# StrongPCB_mixed.net
KiCad netlist of a schematic drawn in Altium Designer
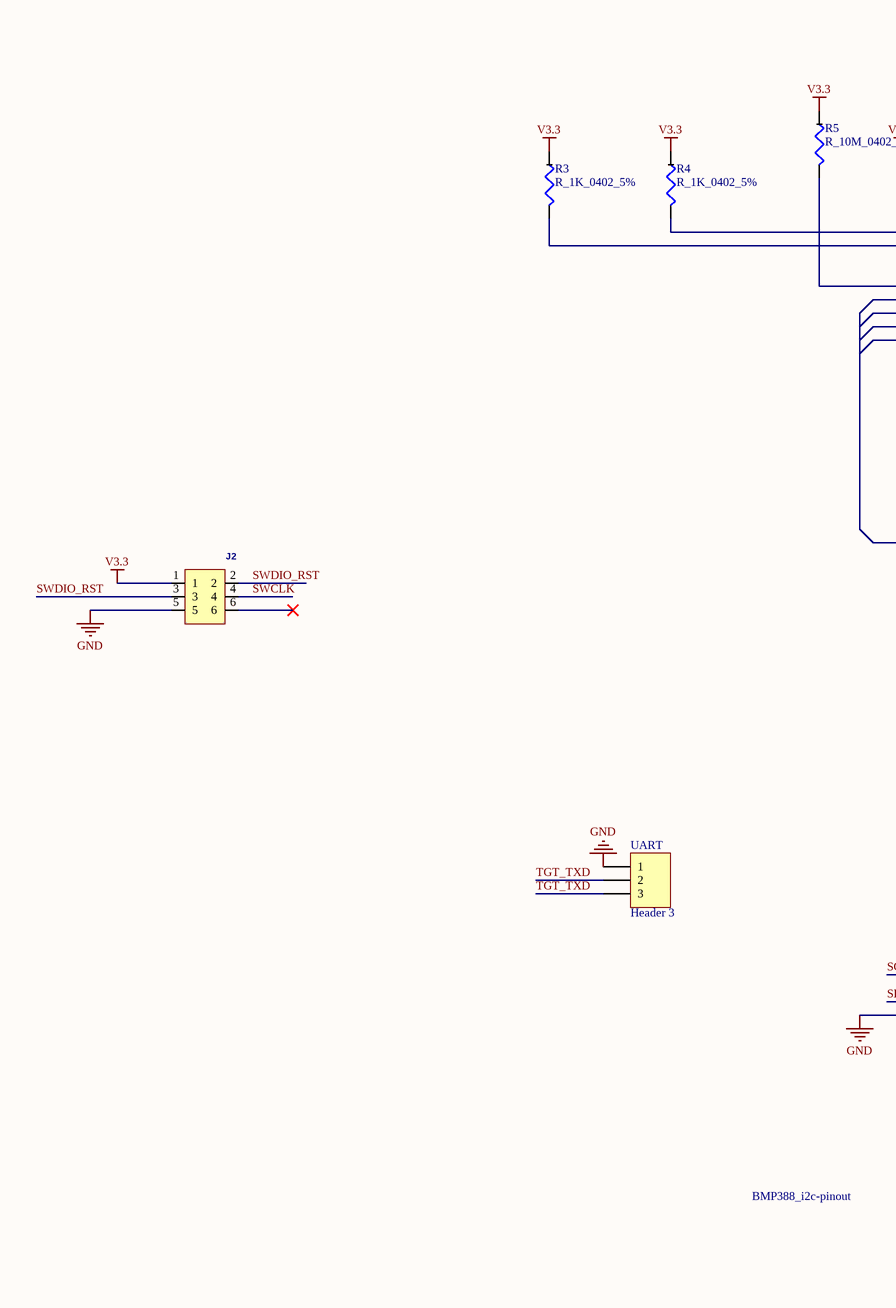
[diagram p0: StrongPCB_mixed.SchDoc, left]
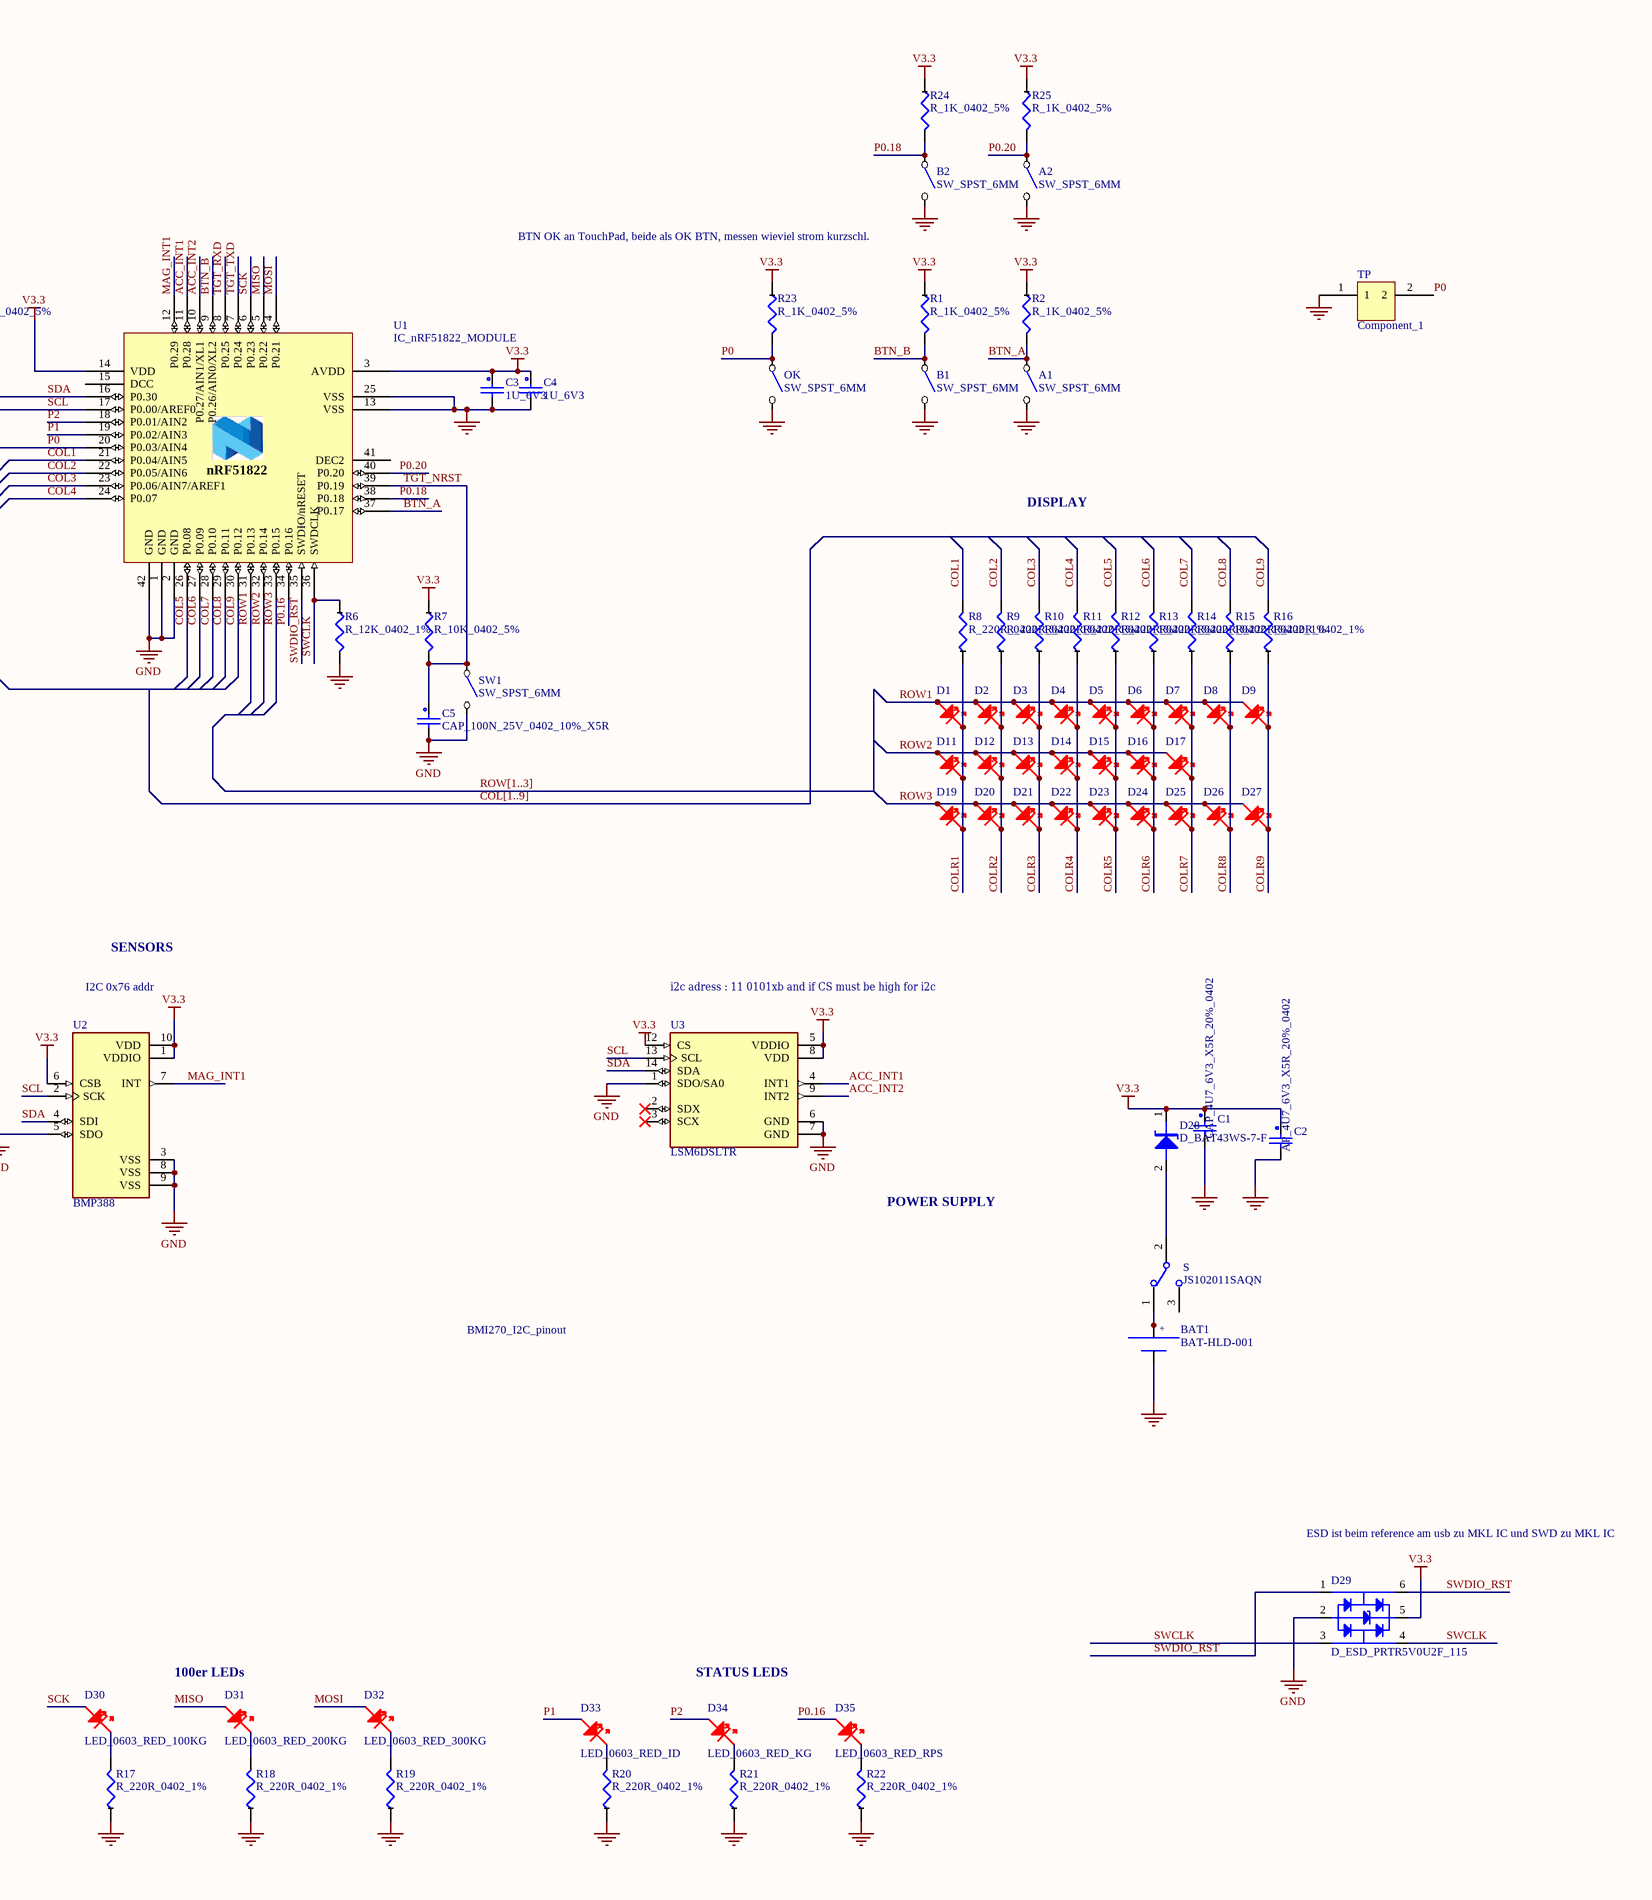
[diagram p1: StrongPCB_mixed.SchDoc, right]

(export (version "E")
  (design (tool "Eeschema 10.0.6"))
  (components
    (comp (ref "A1")
      (value "SW_SPST_6MM")
      (footprint "SW_FSM4JSMA")
      (description "SPST SWITCH 6MM")
      (fields (field (name "PART") "FSM4JSMA") (field (name "MANUFACTURER") "TE CONNECTIVITY / ALCOSWITCH"))
      (libsource (lib "Modulebit_open_V0.4") (part "SW_SPST_6MM"))
    )
    (comp (ref "A2")
      (value "SW_SPST_6MM")
      (footprint "SW_FSM4JSMA")
      (description "SPST SWITCH 6MM")
      (fields (field (name "PART") "FSM4JSMA") (field (name "MANUFACTURER") "TE CONNECTIVITY / ALCOSWITCH"))
      (libsource (lib "Modulebit_open_V0.4") (part "SW_SPST_6MM"))
    )
    (comp (ref "B1")
      (value "SW_SPST_6MM")
      (footprint "SW_FSM4JSMA")
      (description "SPST SWITCH 6MM")
      (fields (field (name "PART") "FSM4JSMA") (field (name "MANUFACTURER") "TE CONNECTIVITY / ALCOSWITCH"))
      (libsource (lib "Modulebit_open_V0.4") (part "SW_SPST_6MM"))
    )
    (comp (ref "B2")
      (value "SW_SPST_6MM")
      (footprint "SW_FSM4JSMA")
      (description "SPST SWITCH 6MM")
      (fields (field (name "PART") "FSM4JSMA") (field (name "MANUFACTURER") "TE CONNECTIVITY / ALCOSWITCH"))
      (libsource (lib "Modulebit_open_V0.4") (part "SW_SPST_6MM"))
    )
    (comp (ref "BAT1")
      (value "BAT-HLD-001")
      (footprint "BAT-HLD-001")
      (description "Battery Retainer Coin, 20.0mm 1 Cell SMD _SMT_ Tab")
      (fields
        (field (name "DIGI-KEY_PART_NUMBER") "BAT-HLD-001-TRCT-ND")
        (field (name "MF") "Linx Technologies")
      )
      (libsource (lib "BAT-HLD-001") (part "BAT-HLD-001"))
    )
    (comp (ref "C1")
      (value "CAP_4U7_6V3_X5R_20%_0402")
      (footprint "c_0402")
      (fields (field (name "PART") "C1005X5R0J475M") (field (name "MANUFACTURER") "TDK"))
      (libsource (lib "Modulebit_open_V0.4") (part "CAP_4U7_6V3_X5R_20%_0402"))
    )
    (comp (ref "C2")
      (value "AP_4U7_6V3_X5R_20%_0402")
      (footprint "c_0402")
      (description "CAP_4U7_6V3_X5R_20%_0402")
      (fields (field (name "PART") "C1005X5R0J475M") (field (name "MANUFACTURER") "TDK"))
      (libsource (lib "Modulebit_open_V0.4") (part "CAP_4U7_6V3_X5R_20%_0402"))
    )
    (comp (ref "C3")
      (value "1U_6V3")
      (footprint "C_0402")
      (description "CAP_1u_6V3_0402_10%_X6S")
      (fields (field (name "MANUFACTURER") "YAGEO") (field (name "PART") "CC0402KRX7R7BB104"))
      (libsource (lib "Modulebit_open_V0.4") (part "CAP_1u_6V3_0402_10%_X6S"))
    )
    (comp (ref "C4")
      (value "1U_6V3")
      (footprint "C_0402")
      (description "CAP_1u_6V3_0402_10%_X6S")
      (fields (field (name "MANUFACTURER") "YAGEO") (field (name "PART") "CC0402KRX7R7BB104"))
      (libsource (lib "Modulebit_open_V0.4") (part "CAP_1u_6V3_0402_10%_X6S"))
    )
    (comp (ref "C5")
      (value "CAP_100N_25V_0402_10%_X5R")
      (footprint "C_0402")
      (fields (field (name "PART") "TMK105BJ104KV-F") (field (name "MANUFACTURER") "TAIYO YUDEN"))
      (libsource (lib "Modulebit_open_V0.4") (part "CAP_100N_25V_0402_10%_X5R"))
    )
    (comp (ref "D1")
      (value "LED_0603_RED")
      (footprint "LED_0603_RED")
      (description "LED RED 0603")
      (fields (field (name "PART") "KP-1608SURC") (field (name "MANUFACTURER") "KINGBRIGHT"))
      (libsource (lib "Modulebit_open_V0.4") (part "LED_0603_RED"))
    )
    (comp (ref "D2")
      (value "LED_0603_RED")
      (footprint "LED_0603_RED")
      (description "LED RED 0603")
      (fields (field (name "PART") "KP-1608SURC") (field (name "MANUFACTURER") "KINGBRIGHT"))
      (libsource (lib "Modulebit_open_V0.4") (part "LED_0603_RED"))
    )
    (comp (ref "D3")
      (value "LED_0603_RED")
      (footprint "LED_0603_RED")
      (description "LED RED 0603")
      (fields (field (name "PART") "KP-1608SURC") (field (name "MANUFACTURER") "KINGBRIGHT"))
      (libsource (lib "Modulebit_open_V0.4") (part "LED_0603_RED"))
    )
    (comp (ref "D4")
      (value "LED_0603_RED")
      (footprint "LED_0603_RED")
      (description "LED RED 0603")
      (fields (field (name "PART") "KP-1608SURC") (field (name "MANUFACTURER") "KINGBRIGHT"))
      (libsource (lib "Modulebit_open_V0.4") (part "LED_0603_RED"))
    )
    (comp (ref "D5")
      (value "LED_0603_RED")
      (footprint "LED_0603_RED")
      (description "LED RED 0603")
      (fields (field (name "PART") "KP-1608SURC") (field (name "MANUFACTURER") "KINGBRIGHT"))
      (libsource (lib "Modulebit_open_V0.4") (part "LED_0603_RED"))
    )
    (comp (ref "D6")
      (value "LED_0603_RED")
      (footprint "LED_0603_RED")
      (description "LED RED 0603")
      (fields (field (name "PART") "KP-1608SURC") (field (name "MANUFACTURER") "KINGBRIGHT"))
      (libsource (lib "Modulebit_open_V0.4") (part "LED_0603_RED"))
    )
    (comp (ref "D7")
      (value "LED_0603_RED")
      (footprint "LED_0603_RED")
      (description "LED RED 0603")
      (fields (field (name "PART") "KP-1608SURC") (field (name "MANUFACTURER") "KINGBRIGHT"))
      (libsource (lib "Modulebit_open_V0.4") (part "LED_0603_RED"))
    )
    (comp (ref "D8")
      (value "LED_0603_RED")
      (footprint "LED_0603_RED")
      (description "LED RED 0603")
      (fields (field (name "PART") "KP-1608SURC") (field (name "MANUFACTURER") "KINGBRIGHT"))
      (libsource (lib "Modulebit_open_V0.4") (part "LED_0603_RED"))
    )
    (comp (ref "D9")
      (value "LED_0603_RED")
      (footprint "LED_0603_RED")
      (description "LED RED 0603")
      (fields (field (name "PART") "KP-1608SURC") (field (name "MANUFACTURER") "KINGBRIGHT"))
      (libsource (lib "Modulebit_open_V0.4") (part "LED_0603_RED"))
    )
    (comp (ref "D11")
      (value "LED_0603_RED")
      (footprint "LED_0603_RED")
      (description "LED RED 0603")
      (fields (field (name "PART") "KP-1608SURC") (field (name "MANUFACTURER") "KINGBRIGHT"))
      (libsource (lib "Modulebit_open_V0.4") (part "LED_0603_RED"))
    )
    (comp (ref "D12")
      (value "LED_0603_RED")
      (footprint "LED_0603_RED")
      (description "LED RED 0603")
      (fields (field (name "PART") "KP-1608SURC") (field (name "MANUFACTURER") "KINGBRIGHT"))
      (libsource (lib "Modulebit_open_V0.4") (part "LED_0603_RED"))
    )
    (comp (ref "D13")
      (value "LED_0603_RED")
      (footprint "LED_0603_RED")
      (description "LED RED 0603")
      (fields (field (name "PART") "KP-1608SURC") (field (name "MANUFACTURER") "KINGBRIGHT"))
      (libsource (lib "Modulebit_open_V0.4") (part "LED_0603_RED"))
    )
    (comp (ref "D14")
      (value "LED_0603_RED")
      (footprint "LED_0603_RED")
      (description "LED RED 0603")
      (fields (field (name "PART") "KP-1608SURC") (field (name "MANUFACTURER") "KINGBRIGHT"))
      (libsource (lib "Modulebit_open_V0.4") (part "LED_0603_RED"))
    )
    (comp (ref "D15")
      (value "LED_0603_RED")
      (footprint "LED_0603_RED")
      (description "LED RED 0603")
      (fields (field (name "PART") "KP-1608SURC") (field (name "MANUFACTURER") "KINGBRIGHT"))
      (libsource (lib "Modulebit_open_V0.4") (part "LED_0603_RED"))
    )
    (comp (ref "D16")
      (value "LED_0603_RED")
      (footprint "LED_0603_RED")
      (description "LED RED 0603")
      (fields (field (name "PART") "KP-1608SURC") (field (name "MANUFACTURER") "KINGBRIGHT"))
      (libsource (lib "Modulebit_open_V0.4") (part "LED_0603_RED"))
    )
    (comp (ref "D17")
      (value "LED_0603_RED")
      (footprint "LED_0603_RED")
      (description "LED RED 0603")
      (fields (field (name "PART") "KP-1608SURC") (field (name "MANUFACTURER") "KINGBRIGHT"))
      (libsource (lib "Modulebit_open_V0.4") (part "LED_0603_RED"))
    )
    (comp (ref "D19")
      (value "LED_0603_RED")
      (footprint "LED_0603_RED")
      (description "LED RED 0603")
      (fields (field (name "PART") "KP-1608SURC") (field (name "MANUFACTURER") "KINGBRIGHT"))
      (libsource (lib "Modulebit_open_V0.4") (part "LED_0603_RED"))
    )
    (comp (ref "D20")
      (value "LED_0603_RED")
      (footprint "LED_0603_RED")
      (description "LED RED 0603")
      (fields (field (name "PART") "KP-1608SURC") (field (name "MANUFACTURER") "KINGBRIGHT"))
      (libsource (lib "Modulebit_open_V0.4") (part "LED_0603_RED"))
    )
    (comp (ref "D21")
      (value "LED_0603_RED")
      (footprint "LED_0603_RED")
      (description "LED RED 0603")
      (fields (field (name "PART") "KP-1608SURC") (field (name "MANUFACTURER") "KINGBRIGHT"))
      (libsource (lib "Modulebit_open_V0.4") (part "LED_0603_RED"))
    )
    (comp (ref "D22")
      (value "LED_0603_RED")
      (footprint "LED_0603_RED")
      (description "LED RED 0603")
      (fields (field (name "PART") "KP-1608SURC") (field (name "MANUFACTURER") "KINGBRIGHT"))
      (libsource (lib "Modulebit_open_V0.4") (part "LED_0603_RED"))
    )
    (comp (ref "D23")
      (value "LED_0603_RED")
      (footprint "LED_0603_RED")
      (description "LED RED 0603")
      (fields (field (name "PART") "KP-1608SURC") (field (name "MANUFACTURER") "KINGBRIGHT"))
      (libsource (lib "Modulebit_open_V0.4") (part "LED_0603_RED"))
    )
    (comp (ref "D24")
      (value "LED_0603_RED")
      (footprint "LED_0603_RED")
      (description "LED RED 0603")
      (fields (field (name "PART") "KP-1608SURC") (field (name "MANUFACTURER") "KINGBRIGHT"))
      (libsource (lib "Modulebit_open_V0.4") (part "LED_0603_RED"))
    )
    (comp (ref "D25")
      (value "LED_0603_RED")
      (footprint "LED_0603_RED")
      (description "LED RED 0603")
      (fields (field (name "PART") "KP-1608SURC") (field (name "MANUFACTURER") "KINGBRIGHT"))
      (libsource (lib "Modulebit_open_V0.4") (part "LED_0603_RED"))
    )
    (comp (ref "D26")
      (value "LED_0603_RED")
      (footprint "LED_0603_RED")
      (description "LED RED 0603")
      (fields (field (name "PART") "KP-1608SURC") (field (name "MANUFACTURER") "KINGBRIGHT"))
      (libsource (lib "Modulebit_open_V0.4") (part "LED_0603_RED"))
    )
    (comp (ref "D27")
      (value "LED_0603_RED")
      (footprint "LED_0603_RED")
      (description "LED RED 0603")
      (fields (field (name "PART") "KP-1608SURC") (field (name "MANUFACTURER") "KINGBRIGHT"))
      (libsource (lib "Modulebit_open_V0.4") (part "LED_0603_RED"))
    )
    (comp (ref "D28")
      (value "D_BAT43WS-7-F")
      (footprint "SOD323")
      (description "Schottky 200mA 30V 0.5uA@25Vr")
      (fields (field (name "MANUFACTURER") "Diodes Incorporated") (field (name "PART") "BAT43WS-7-F"))
      (libsource (lib "Modulebit_open_V0.4") (part "D_BAT43WS-7-F"))
    )
    (comp (ref "D29")
      (value "D_ESD_PRTR5V0U2F_115")
      (footprint "SOT886")
      (description "Ultra low capacitance double rail-to-rail ESD protection")
      (fields (field (name "MANUFACTURER") "NXP") (field (name "PART") "PRTR5V0U2F_115"))
      (libsource (lib "Modulebit_open_V0.4") (part "D_ESD_PRTR5V0U2F_115"))
    )
    (comp (ref "D30")
      (value "LED_0603_RED_100KG")
      (footprint "LED_0603_RED")
      (description "LED RED 0603")
      (fields (field (name "PART") "KP-1608SURC") (field (name "MANUFACTURER") "KINGBRIGHT"))
      (libsource (lib "Modulebit_open_V0.4") (part "LED_0603_RED"))
    )
    (comp (ref "D31")
      (value "LED_0603_RED_200KG")
      (footprint "LED_0603_RED")
      (description "LED RED 0603")
      (fields (field (name "PART") "KP-1608SURC") (field (name "MANUFACTURER") "KINGBRIGHT"))
      (libsource (lib "Modulebit_open_V0.4") (part "LED_0603_RED"))
    )
    (comp (ref "D32")
      (value "LED_0603_RED_300KG")
      (footprint "LED_0603_RED")
      (description "LED RED 0603")
      (fields (field (name "PART") "KP-1608SURC") (field (name "MANUFACTURER") "KINGBRIGHT"))
      (libsource (lib "Modulebit_open_V0.4") (part "LED_0603_RED"))
    )
    (comp (ref "D33")
      (value "LED_0603_RED_ID")
      (footprint "LED_0603_RED")
      (description "LED RED 0603")
      (fields (field (name "PART") "KP-1608SURC") (field (name "MANUFACTURER") "KINGBRIGHT"))
      (libsource (lib "Modulebit_open_V0.4") (part "LED_0603_RED"))
    )
    (comp (ref "D34")
      (value "LED_0603_RED_KG")
      (footprint "LED_0603_RED")
      (description "LED RED 0603")
      (fields (field (name "PART") "KP-1608SURC") (field (name "MANUFACTURER") "KINGBRIGHT"))
      (libsource (lib "Modulebit_open_V0.4") (part "LED_0603_RED"))
    )
    (comp (ref "D35")
      (value "LED_0603_RED_RPS")
      (footprint "LED_0603_RED")
      (description "LED RED 0603")
      (fields (field (name "PART") "KP-1608SURC") (field (name "MANUFACTURER") "KINGBRIGHT"))
      (libsource (lib "Modulebit_open_V0.4") (part "LED_0603_RED"))
    )
    (comp (ref "J2")
      (value "Sockets & Adapters J-Link 6-pin Needle Adapter   Source:  Datasheet")
      (footprint "J-Link 6-pin Needle Adapter no legs")
      (fields
        (field (name "MANUFACTURER_PART_NUMBER") "8.06.16")
        (field (name "MOUSER_PART_NUMBER") "943-8.06.16")
      )
      (libsource (lib "J-Link 6-pin") (part "J-Link Connector"))
    )
    (comp (ref "OK")
      (value "SW_SPST_6MM")
      (footprint "SW_FSM4JSMA")
      (description "SPST SWITCH 6MM")
      (fields (field (name "PART") "FSM4JSMA") (field (name "MANUFACTURER") "TE CONNECTIVITY / ALCOSWITCH"))
      (libsource (lib "Modulebit_open_V0.4") (part "SW_SPST_6MM"))
    )
    (comp (ref "R1")
      (value "R_1K_0402_5%")
      (footprint "R_0402")
      (libsource (lib "Modulebit_open_V0.4") (part "R_1K_0402_5%"))
    )
    (comp (ref "R2")
      (value "R_1K_0402_5%")
      (footprint "R_0402")
      (libsource (lib "Modulebit_open_V0.4") (part "R_1K_0402_5%"))
    )
    (comp (ref "R3")
      (value "R_1K_0402_5%")
      (footprint "R_0402")
      (libsource (lib "Modulebit_open_V0.4") (part "R_1K_0402_5%"))
    )
    (comp (ref "R4")
      (value "R_1K_0402_5%")
      (footprint "R_0402")
      (libsource (lib "Modulebit_open_V0.4") (part "R_1K_0402_5%"))
    )
    (comp (ref "R5")
      (value "R_10M_0402_5%")
      (footprint "R_0402")
      (fields (field (name "PART") "RC0603FR-0710ML") (field (name "MANUFACTURER") "YAGEO"))
      (libsource (lib "Modulebit_open_V0.4") (part "R_10M_0402_5%"))
    )
    (comp (ref "R6")
      (value "R_12K_0402_1%")
      (footprint "R_0402")
      (libsource (lib "Modulebit_open_V0.4") (part "R_12K_0402_1%"))
    )
    (comp (ref "R7")
      (value "R_10K_0402_5%")
      (footprint "R_0402")
      (libsource (lib "Modulebit_open_V0.4") (part "R_10K_0402_5%"))
    )
    (comp (ref "R8")
      (value "R_220R_0402_1%")
      (footprint "R_0402")
      (libsource (lib "custom_modulebit_Lib") (part "R_220R_0402_1%"))
    )
    (comp (ref "R9")
      (value "R_220R_0402_1%")
      (footprint "R_0402")
      (libsource (lib "custom_modulebit_Lib") (part "R_220R_0402_1%"))
    )
    (comp (ref "R10")
      (value "R_220R_0402_1%")
      (footprint "R_0402")
      (libsource (lib "custom_modulebit_Lib") (part "R_220R_0402_1%"))
    )
    (comp (ref "R11")
      (value "R_220R_0402_1%")
      (footprint "R_0402")
      (libsource (lib "custom_modulebit_Lib") (part "R_220R_0402_1%"))
    )
    (comp (ref "R12")
      (value "R_220R_0402_1%")
      (footprint "R_0402")
      (libsource (lib "custom_modulebit_Lib") (part "R_220R_0402_1%"))
    )
    (comp (ref "R13")
      (value "R_220R_0402_1%")
      (footprint "R_0402")
      (libsource (lib "custom_modulebit_Lib") (part "R_220R_0402_1%"))
    )
    (comp (ref "R14")
      (value "R_220R_0402_1%")
      (footprint "R_0402")
      (libsource (lib "custom_modulebit_Lib") (part "R_220R_0402_1%"))
    )
    (comp (ref "R15")
      (value "R_220R_0402_1%")
      (footprint "R_0402")
      (libsource (lib "custom_modulebit_Lib") (part "R_220R_0402_1%"))
    )
    (comp (ref "R16")
      (value "R_220R_0402_1%")
      (footprint "R_0402")
      (libsource (lib "custom_modulebit_Lib") (part "R_220R_0402_1%"))
    )
    (comp (ref "R17")
      (value "R_220R_0402_1%")
      (footprint "R_0402")
      (libsource (lib "custom_modulebit_Lib") (part "R_220R_0402_1%"))
    )
    (comp (ref "R18")
      (value "R_220R_0402_1%")
      (footprint "R_0402")
      (libsource (lib "custom_modulebit_Lib") (part "R_220R_0402_1%"))
    )
    (comp (ref "R19")
      (value "R_220R_0402_1%")
      (footprint "R_0402")
      (libsource (lib "custom_modulebit_Lib") (part "R_220R_0402_1%"))
    )
    (comp (ref "R20")
      (value "R_220R_0402_1%")
      (footprint "R_0402")
      (libsource (lib "custom_modulebit_Lib") (part "R_220R_0402_1%"))
    )
    (comp (ref "R21")
      (value "R_220R_0402_1%")
      (footprint "R_0402")
      (libsource (lib "custom_modulebit_Lib") (part "R_220R_0402_1%"))
    )
    (comp (ref "R22")
      (value "R_220R_0402_1%")
      (footprint "R_0402")
      (libsource (lib "custom_modulebit_Lib") (part "R_220R_0402_1%"))
    )
    (comp (ref "R23")
      (value "R_1K_0402_5%")
      (footprint "R_0402")
      (libsource (lib "Modulebit_open_V0.4") (part "R_1K_0402_5%"))
    )
    (comp (ref "R24")
      (value "R_1K_0402_5%")
      (footprint "R_0402")
      (libsource (lib "Modulebit_open_V0.4") (part "R_1K_0402_5%"))
    )
    (comp (ref "R25")
      (value "R_1K_0402_5%")
      (footprint "R_0402")
      (libsource (lib "Modulebit_open_V0.4") (part "R_1K_0402_5%"))
    )
    (comp (ref "S")
      (value "JS102011SAQN")
      (footprint "SW_JS102011SAQN")
      (description "Slide Switch SPDT Surface Mount, Right Angle")
      (fields (field (name "MF") "C&K"))
      (libsource (lib "JS102011SAQN_SWITCH") (part "JS102011SAQN"))
    )
    (comp (ref "SW1")
      (value "SW_SPST_6MM")
      (footprint "SW_FSM4JSMA")
      (description "SPST SWITCH 6MM")
      (fields (field (name "PART") "FSM4JSMA") (field (name "MANUFACTURER") "TE CONNECTIVITY / ALCOSWITCH"))
      (libsource (lib "Modulebit_open_V0.4") (part "SW_SPST_6MM"))
    )
    (comp (ref "TP")
      (value "Component_1")
      (footprint "PCBComponent_1")
      (libsource (lib "TP") (part "Component_1"))
    )
    (comp (ref "U1")
      (value "IC_nRF51822_MODULE")
      (footprint "IC_nRF51822_MODULE_PASTE")
      (description "RF System on a Chip - SoC 2.4GHz BT low Energy 256KB Flash 16KB Ram")
      (fields (field (name "MANUFACTURER") "RAYTAC") (field (name "PART") "MDBT40-256V3"))
      (libsource (lib "Modulebit_open_V0.4") (part "IC_nRF51822_MODULE"))
    )
    (comp (ref "U2")
      (value "BMP388")
      (footprint "PQFN50P200X200X80-10N")
      (description "Pressure Sensor 4.35PSI ~ 18.13PSI _30kPa ~ 125kPa_ Absolute 10-WFLGA")
      (fields (field (name "DIGI-KEY_PART_NUMBER") "828-1079-1-ND") (field (name "MF") "Bosch Sensortec"))
      (libsource (lib "BMP388") (part "BMP388"))
    )
    (comp (ref "U3")
      (value "LSM6DSLTR")
      (footprint "PQFN50P300X250X86-14N")
      (description "Accelerometer, Gyroscope, Temperature, 6 Axis Sensor IÂ²C, SPI Output")
      (fields (field (name "MF") "STMicroelectronics"))
      (libsource (lib "LSM6DSLTR") (part "LSM6DSLTR"))
    )
    (comp (ref "UART")
      (value "Header 3")
      (footprint "HDR1X3")
      (description "Header, 3-Pin")
      (fields (field (name "PUBLISHER") "Altium Limited"))
      (libsource (lib "Miscellaneous Connectors") (part "Header 3"))
    )
  )
  (nets
    (net (code "1") (name "/ACC_INT1") (class "Default")
      (node (ref "U1") (pin "11") (pinfunction "P0.28_11") (pintype "bidirectional"))
      (node (ref "U3") (pin "4") (pinfunction "INT1_4") (pintype "output"))
    )
    (net (code "2") (name "/ACC_INT2") (class "Default")
      (node (ref "U1") (pin "10") (pinfunction "P0.27/AIN1/XL1_10") (pintype "bidirectional"))
      (node (ref "U3") (pin "9") (pinfunction "INT2_9") (pintype "output"))
    )
    (net (code "3") (name "/BTN_A") (class "Default")
      (node (ref "A1") (pin "1") (pinfunction "1_1") (pintype "passive"))
      (node (ref "R2") (pin "2") (pinfunction "2_2") (pintype "passive"))
      (node (ref "U1") (pin "37") (pinfunction "P0.17_37") (pintype "bidirectional"))
    )
    (net (code "4") (name "/BTN_B") (class "Default")
      (node (ref "B1") (pin "1") (pinfunction "1_1") (pintype "passive"))
      (node (ref "R1") (pin "2") (pinfunction "2_2") (pintype "passive"))
      (node (ref "U1") (pin "9") (pinfunction "P0.26/AIN0/XL2_9") (pintype "bidirectional"))
    )
    (net (code "5") (name "/COL1") (class "Default")
      (node (ref "R8") (pin "2") (pinfunction "2_2") (pintype "passive"))
      (node (ref "U1") (pin "21") (pinfunction "P0.04/AIN5_21") (pintype "bidirectional"))
    )
    (net (code "6") (name "/COL2") (class "Default")
      (node (ref "R9") (pin "2") (pinfunction "2_2") (pintype "passive"))
      (node (ref "U1") (pin "22") (pinfunction "P0.05/AIN6_22") (pintype "bidirectional"))
    )
    (net (code "7") (name "/COL3") (class "Default")
      (node (ref "R10") (pin "2") (pinfunction "2_2") (pintype "passive"))
      (node (ref "U1") (pin "23") (pinfunction "P0.06/AIN7/AREF1_23") (pintype "bidirectional"))
    )
    (net (code "8") (name "/COL4") (class "Default")
      (node (ref "R11") (pin "2") (pinfunction "2_2") (pintype "passive"))
      (node (ref "U1") (pin "24") (pinfunction "P0.07_24") (pintype "bidirectional"))
    )
    (net (code "9") (name "/COL5") (class "Default")
      (node (ref "R12") (pin "2") (pinfunction "2_2") (pintype "passive"))
      (node (ref "U1") (pin "26") (pinfunction "P0.08_26") (pintype "bidirectional"))
    )
    (net (code "10") (name "/COL6") (class "Default")
      (node (ref "R13") (pin "2") (pinfunction "2_2") (pintype "passive"))
      (node (ref "U1") (pin "27") (pinfunction "P0.09_27") (pintype "bidirectional"))
    )
    (net (code "11") (name "/COL7") (class "Default")
      (node (ref "R14") (pin "2") (pinfunction "2_2") (pintype "passive"))
      (node (ref "U1") (pin "28") (pinfunction "P0.10_28") (pintype "bidirectional"))
    )
    (net (code "12") (name "/COL8") (class "Default")
      (node (ref "R15") (pin "2") (pinfunction "2_2") (pintype "passive"))
      (node (ref "U1") (pin "29") (pinfunction "P0.11_29") (pintype "bidirectional"))
    )
    (net (code "13") (name "/COL9") (class "Default")
      (node (ref "R16") (pin "2") (pinfunction "2_2") (pintype "passive"))
      (node (ref "U1") (pin "30") (pinfunction "P0.12_30") (pintype "bidirectional"))
    )
    (net (code "14") (name "/COLR1") (class "Default")
      (node (ref "D1") (pin "K") (pinfunction "K_K") (pintype "passive"))
      (node (ref "D11") (pin "K") (pinfunction "K_K") (pintype "passive"))
      (node (ref "D19") (pin "K") (pinfunction "K_K") (pintype "passive"))
      (node (ref "R8") (pin "1") (pinfunction "1_1") (pintype "passive"))
    )
    (net (code "15") (name "/COLR2") (class "Default")
      (node (ref "D12") (pin "K") (pinfunction "K_K") (pintype "passive"))
      (node (ref "D2") (pin "K") (pinfunction "K_K") (pintype "passive"))
      (node (ref "D20") (pin "K") (pinfunction "K_K") (pintype "passive"))
      (node (ref "R9") (pin "1") (pinfunction "1_1") (pintype "passive"))
    )
    (net (code "16") (name "/COLR3") (class "Default")
      (node (ref "D13") (pin "K") (pinfunction "K_K") (pintype "passive"))
      (node (ref "D21") (pin "K") (pinfunction "K_K") (pintype "passive"))
      (node (ref "D3") (pin "K") (pinfunction "K_K") (pintype "passive"))
      (node (ref "R10") (pin "1") (pinfunction "1_1") (pintype "passive"))
    )
    (net (code "17") (name "/COLR4") (class "Default")
      (node (ref "D14") (pin "K") (pinfunction "K_K") (pintype "passive"))
      (node (ref "D22") (pin "K") (pinfunction "K_K") (pintype "passive"))
      (node (ref "D4") (pin "K") (pinfunction "K_K") (pintype "passive"))
      (node (ref "R11") (pin "1") (pinfunction "1_1") (pintype "passive"))
    )
    (net (code "18") (name "/COLR5") (class "Default")
      (node (ref "D15") (pin "K") (pinfunction "K_K") (pintype "passive"))
      (node (ref "D23") (pin "K") (pinfunction "K_K") (pintype "passive"))
      (node (ref "D5") (pin "K") (pinfunction "K_K") (pintype "passive"))
      (node (ref "R12") (pin "1") (pinfunction "1_1") (pintype "passive"))
    )
    (net (code "19") (name "/COLR6") (class "Default")
      (node (ref "D16") (pin "K") (pinfunction "K_K") (pintype "passive"))
      (node (ref "D24") (pin "K") (pinfunction "K_K") (pintype "passive"))
      (node (ref "D6") (pin "K") (pinfunction "K_K") (pintype "passive"))
      (node (ref "R13") (pin "1") (pinfunction "1_1") (pintype "passive"))
    )
    (net (code "20") (name "/COLR7") (class "Default")
      (node (ref "D17") (pin "K") (pinfunction "K_K") (pintype "passive"))
      (node (ref "D25") (pin "K") (pinfunction "K_K") (pintype "passive"))
      (node (ref "D7") (pin "K") (pinfunction "K_K") (pintype "passive"))
      (node (ref "R14") (pin "1") (pinfunction "1_1") (pintype "passive"))
    )
    (net (code "21") (name "/COLR8") (class "Default")
      (node (ref "D26") (pin "K") (pinfunction "K_K") (pintype "passive"))
      (node (ref "D8") (pin "K") (pinfunction "K_K") (pintype "passive"))
      (node (ref "R15") (pin "1") (pinfunction "1_1") (pintype "passive"))
    )
    (net (code "22") (name "/COLR9") (class "Default")
      (node (ref "D27") (pin "K") (pinfunction "K_K") (pintype "passive"))
      (node (ref "D9") (pin "K") (pinfunction "K_K") (pintype "passive"))
      (node (ref "R16") (pin "1") (pinfunction "1_1") (pintype "passive"))
    )
    (net (code "24") (name "/MAG_INT1") (class "Default")
      (node (ref "U1") (pin "12") (pinfunction "P0.29_12") (pintype "bidirectional"))
      (node (ref "U2") (pin "7") (pinfunction "INT_7") (pintype "output"))
    )
    (net (code "25") (name "/MISO") (class "Default")
      (node (ref "D31") (pin "A") (pinfunction "A_A") (pintype "passive"))
      (node (ref "U1") (pin "5") (pinfunction "P0.22_5") (pintype "bidirectional"))
    )
    (net (code "26") (name "/MOSI") (class "Default")
      (node (ref "D32") (pin "A") (pinfunction "A_A") (pintype "passive"))
      (node (ref "U1") (pin "4") (pinfunction "P0.21_4") (pintype "bidirectional"))
    )
    (net (code "27") (name "/P0") (class "Default")
      (node (ref "OK") (pin "1") (pinfunction "1_1") (pintype "passive"))
      (node (ref "R23") (pin "2") (pinfunction "2_2") (pintype "passive"))
      (node (ref "R5") (pin "2") (pinfunction "2_2") (pintype "passive"))
      (node (ref "TP") (pin "2") (pinfunction "2_2") (pintype "passive"))
      (node (ref "U1") (pin "20") (pinfunction "P0.03/AIN4_20") (pintype "bidirectional"))
    )
    (net (code "28") (name "/P0.16") (class "Default")
      (node (ref "D35") (pin "A") (pinfunction "A_A") (pintype "passive"))
      (node (ref "U1") (pin "34") (pinfunction "P0.16_34") (pintype "bidirectional"))
    )
    (net (code "29") (name "/P0.18") (class "Default")
      (node (ref "B2") (pin "1") (pinfunction "1_1") (pintype "passive"))
      (node (ref "R24") (pin "2") (pinfunction "2_2") (pintype "passive"))
      (node (ref "U1") (pin "38") (pinfunction "P0.18_38") (pintype "bidirectional"))
    )
    (net (code "30") (name "/P0.20") (class "Default")
      (node (ref "A2") (pin "1") (pinfunction "1_1") (pintype "passive"))
      (node (ref "R25") (pin "2") (pinfunction "2_2") (pintype "passive"))
      (node (ref "U1") (pin "40") (pinfunction "P0.20_40") (pintype "bidirectional"))
    )
    (net (code "31") (name "/P1") (class "Default")
      (node (ref "D33") (pin "A") (pinfunction "A_A") (pintype "passive"))
      (node (ref "U1") (pin "19") (pinfunction "P0.02/AIN3_19") (pintype "bidirectional"))
    )
    (net (code "32") (name "/P2") (class "Default")
      (node (ref "D34") (pin "A") (pinfunction "A_A") (pintype "passive"))
      (node (ref "U1") (pin "18") (pinfunction "P0.01/AIN2_18") (pintype "bidirectional"))
    )
    (net (code "33") (name "/ROW1") (class "Default")
      (node (ref "D1") (pin "A") (pinfunction "A_A") (pintype "passive"))
      (node (ref "D2") (pin "A") (pinfunction "A_A") (pintype "passive"))
      (node (ref "D3") (pin "A") (pinfunction "A_A") (pintype "passive"))
      (node (ref "D4") (pin "A") (pinfunction "A_A") (pintype "passive"))
      (node (ref "D5") (pin "A") (pinfunction "A_A") (pintype "passive"))
      (node (ref "D6") (pin "A") (pinfunction "A_A") (pintype "passive"))
      (node (ref "D7") (pin "A") (pinfunction "A_A") (pintype "passive"))
      (node (ref "D8") (pin "A") (pinfunction "A_A") (pintype "passive"))
      (node (ref "D9") (pin "A") (pinfunction "A_A") (pintype "passive"))
      (node (ref "U1") (pin "31") (pinfunction "P0.13_31") (pintype "bidirectional"))
    )
    (net (code "34") (name "/ROW2") (class "Default")
      (node (ref "D11") (pin "A") (pinfunction "A_A") (pintype "passive"))
      (node (ref "D12") (pin "A") (pinfunction "A_A") (pintype "passive"))
      (node (ref "D13") (pin "A") (pinfunction "A_A") (pintype "passive"))
      (node (ref "D14") (pin "A") (pinfunction "A_A") (pintype "passive"))
      (node (ref "D15") (pin "A") (pinfunction "A_A") (pintype "passive"))
      (node (ref "D16") (pin "A") (pinfunction "A_A") (pintype "passive"))
      (node (ref "D17") (pin "A") (pinfunction "A_A") (pintype "passive"))
      (node (ref "U1") (pin "32") (pinfunction "P0.14_32") (pintype "bidirectional"))
    )
    (net (code "35") (name "/ROW3") (class "Default")
      (node (ref "D19") (pin "A") (pinfunction "A_A") (pintype "passive"))
      (node (ref "D20") (pin "A") (pinfunction "A_A") (pintype "passive"))
      (node (ref "D21") (pin "A") (pinfunction "A_A") (pintype "passive"))
      (node (ref "D22") (pin "A") (pinfunction "A_A") (pintype "passive"))
      (node (ref "D23") (pin "A") (pinfunction "A_A") (pintype "passive"))
      (node (ref "D24") (pin "A") (pinfunction "A_A") (pintype "passive"))
      (node (ref "D25") (pin "A") (pinfunction "A_A") (pintype "passive"))
      (node (ref "D26") (pin "A") (pinfunction "A_A") (pintype "passive"))
      (node (ref "D27") (pin "A") (pinfunction "A_A") (pintype "passive"))
      (node (ref "U1") (pin "33") (pinfunction "P0.15_33") (pintype "bidirectional"))
    )
    (net (code "37") (name "/SCK") (class "Default")
      (node (ref "D30") (pin "A") (pinfunction "A_A") (pintype "passive"))
      (node (ref "U1") (pin "6") (pinfunction "P0.23_6") (pintype "bidirectional"))
    )
    (net (code "38") (name "/SCL") (class "Default")
      (node (ref "R3") (pin "2") (pinfunction "2_2") (pintype "passive"))
      (node (ref "U1") (pin "17") (pinfunction "P0.00/AREF0_17") (pintype "bidirectional"))
      (node (ref "U2") (pin "2") (pinfunction "SCK_2") (pintype "input"))
      (node (ref "U3") (pin "13") (pinfunction "SCL_13") (pintype "input"))
    )
    (net (code "39") (name "/SDA") (class "Default")
      (node (ref "R4") (pin "2") (pinfunction "2_2") (pintype "passive"))
      (node (ref "U1") (pin "16") (pinfunction "P0.30_16") (pintype "bidirectional"))
      (node (ref "U2") (pin "4") (pinfunction "SDI_4") (pintype "bidirectional"))
      (node (ref "U3") (pin "14") (pinfunction "SDA_14") (pintype "bidirectional"))
    )
    (net (code "40") (name "/SWCLK") (class "Default")
      (node (ref "D29") (pin "3") (pinfunction "3_3") (pintype "passive"))
      (node (ref "D29") (pin "4") (pinfunction "4_4") (pintype "passive"))
      (node (ref "J2") (pin "4") (pinfunction "4_4") (pintype "passive"))
      (node (ref "R6") (pin "1") (pinfunction "1_1") (pintype "passive"))
      (node (ref "U1") (pin "36") (pinfunction "SWDCLK_36") (pintype "input"))
    )
    (net (code "41") (name "/SWDIO_RST") (class "Default")
      (node (ref "D29") (pin "1") (pinfunction "1_1") (pintype "passive"))
      (node (ref "D29") (pin "6") (pinfunction "6_6") (pintype "passive"))
      (node (ref "J2") (pin "2") (pinfunction "2_2") (pintype "passive"))
      (node (ref "J2") (pin "3") (pinfunction "3_3") (pintype "passive"))
      (node (ref "U1") (pin "35") (pinfunction "SWDIO/nRESET_35") (pintype "input"))
    )
    (net (code "42") (name "/TGT_NRST") (class "Default")
      (node (ref "C5") (pin "1") (pinfunction "1_1") (pintype "passive"))
      (node (ref "R7") (pin "2") (pinfunction "2_2") (pintype "passive"))
      (node (ref "SW1") (pin "1") (pinfunction "1_1") (pintype "passive"))
      (node (ref "U1") (pin "39") (pinfunction "P0.19_39") (pintype "bidirectional"))
    )
    (net (code "43") (name "/TGT_RXD") (class "Default")
      (node (ref "U1") (pin "8") (pinfunction "P0.25_8") (pintype "bidirectional"))
    )
    (net (code "44") (name "/TGT_TXD") (class "Default")
      (node (ref "U1") (pin "7") (pinfunction "P0.24_7") (pintype "bidirectional"))
      (node (ref "UART") (pin "2") (pinfunction "2_2") (pintype "passive"))
      (node (ref "UART") (pin "3") (pinfunction "3_3") (pintype "passive"))
    )
    (net (code "45") (name "GND") (class "Default")
      (node (ref "A1") (pin "2") (pinfunction "2_2") (pintype "passive"))
      (node (ref "A2") (pin "2") (pinfunction "2_2") (pintype "passive"))
      (node (ref "B1") (pin "2") (pinfunction "2_2") (pintype "passive"))
      (node (ref "B2") (pin "2") (pinfunction "2_2") (pintype "passive"))
      (node (ref "BAT1") (pin "NEG") (pinfunction "NEG_NEG") (pintype "bidirectional"))
      (node (ref "C1") (pin "2") (pinfunction "2_2") (pintype "passive"))
      (node (ref "C2") (pin "2") (pinfunction "2_2") (pintype "passive"))
      (node (ref "C3") (pin "2") (pinfunction "2_2") (pintype "passive"))
      (node (ref "C4") (pin "2") (pinfunction "2_2") (pintype "passive"))
      (node (ref "C5") (pin "2") (pinfunction "2_2") (pintype "passive"))
      (node (ref "D29") (pin "2") (pinfunction "2_2") (pintype "passive"))
      (node (ref "J2") (pin "5") (pinfunction "5_5") (pintype "passive"))
      (node (ref "OK") (pin "2") (pinfunction "2_2") (pintype "passive"))
      (node (ref "R17") (pin "1") (pinfunction "1_1") (pintype "passive"))
      (node (ref "R18") (pin "1") (pinfunction "1_1") (pintype "passive"))
      (node (ref "R19") (pin "1") (pinfunction "1_1") (pintype "passive"))
      (node (ref "R20") (pin "1") (pinfunction "1_1") (pintype "passive"))
      (node (ref "R21") (pin "1") (pinfunction "1_1") (pintype "passive"))
      (node (ref "R22") (pin "1") (pinfunction "1_1") (pintype "passive"))
      (node (ref "R6") (pin "2") (pinfunction "2_2") (pintype "passive"))
      (node (ref "SW1") (pin "2") (pinfunction "2_2") (pintype "passive"))
      (node (ref "TP") (pin "1") (pinfunction "1_1") (pintype "passive"))
      (node (ref "U1") (pin "1") (pinfunction "GND_1") (pintype "power_in"))
      (node (ref "U1") (pin "13") (pinfunction "VSS_13") (pintype "power_in"))
      (node (ref "U1") (pin "2") (pinfunction "GND_2") (pintype "power_in"))
      (node (ref "U1") (pin "25") (pinfunction "VSS_25") (pintype "power_in"))
      (node (ref "U1") (pin "42") (pinfunction "GND_42") (pintype "power_in"))
      (node (ref "U2") (pin "3") (pinfunction "VSS_3") (pintype "power_in"))
      (node (ref "U2") (pin "5") (pinfunction "SDO_5") (pintype "bidirectional"))
      (node (ref "U2") (pin "8") (pinfunction "VSS_8") (pintype "power_in"))
      (node (ref "U2") (pin "9") (pinfunction "VSS_9") (pintype "power_in"))
      (node (ref "U3") (pin "1") (pinfunction "SDO/SA0_1") (pintype "bidirectional"))
      (node (ref "U3") (pin "6") (pinfunction "GND_6") (pintype "power_in"))
      (node (ref "U3") (pin "7") (pinfunction "GND_7") (pintype "power_in"))
      (node (ref "UART") (pin "1") (pinfunction "1_1") (pintype "passive"))
    )
    (net (code "46") (name "Net-(BAT1-Pad+@1)") (class "Default")
      (node (ref "BAT1") (pin "+@1") (pinfunction "+@1_+@1") (pintype "bidirectional"))
      (node (ref "BAT1") (pin "+@2") (pinfunction "+@2_+@2") (pintype "bidirectional"))
      (node (ref "S") (pin "1") (pinfunction "1_1") (pintype "passive"))
    )
    (net (code "47") (name "Net-(D28-A)") (class "Default")
      (node (ref "D28") (pin "2") (pinfunction "A_2") (pintype "passive"))
      (node (ref "S") (pin "2") (pinfunction "2_2") (pintype "passive"))
    )
    (net (code "48") (name "Net-(D30-PadK)") (class "Default")
      (node (ref "D30") (pin "K") (pinfunction "K_K") (pintype "passive"))
      (node (ref "R17") (pin "2") (pinfunction "2_2") (pintype "passive"))
    )
    (net (code "49") (name "Net-(D31-PadK)") (class "Default")
      (node (ref "D31") (pin "K") (pinfunction "K_K") (pintype "passive"))
      (node (ref "R18") (pin "2") (pinfunction "2_2") (pintype "passive"))
    )
    (net (code "50") (name "Net-(D32-PadK)") (class "Default")
      (node (ref "D32") (pin "K") (pinfunction "K_K") (pintype "passive"))
      (node (ref "R19") (pin "2") (pinfunction "2_2") (pintype "passive"))
    )
    (net (code "51") (name "Net-(D33-PadK)") (class "Default")
      (node (ref "D33") (pin "K") (pinfunction "K_K") (pintype "passive"))
      (node (ref "R20") (pin "2") (pinfunction "2_2") (pintype "passive"))
    )
    (net (code "52") (name "Net-(D34-PadK)") (class "Default")
      (node (ref "D34") (pin "K") (pinfunction "K_K") (pintype "passive"))
      (node (ref "R21") (pin "2") (pinfunction "2_2") (pintype "passive"))
    )
    (net (code "53") (name "Net-(D35-PadK)") (class "Default")
      (node (ref "D35") (pin "K") (pinfunction "K_K") (pintype "passive"))
      (node (ref "R22") (pin "2") (pinfunction "2_2") (pintype "passive"))
    )
    (net (code "54") (name "V3.3") (class "Default")
      (node (ref "C1") (pin "1") (pinfunction "1_1") (pintype "passive"))
      (node (ref "C2") (pin "1") (pinfunction "1_1") (pintype "passive"))
      (node (ref "C3") (pin "1") (pinfunction "1_1") (pintype "passive"))
      (node (ref "C4") (pin "1") (pinfunction "1_1") (pintype "passive"))
      (node (ref "D28") (pin "1") (pinfunction "K_1") (pintype "passive"))
      (node (ref "D29") (pin "5") (pinfunction "5_5") (pintype "passive"))
      (node (ref "J2") (pin "1") (pinfunction "1_1") (pintype "passive"))
      (node (ref "R1") (pin "1") (pinfunction "1_1") (pintype "passive"))
      (node (ref "R2") (pin "1") (pinfunction "1_1") (pintype "passive"))
      (node (ref "R23") (pin "1") (pinfunction "1_1") (pintype "passive"))
      (node (ref "R24") (pin "1") (pinfunction "1_1") (pintype "passive"))
      (node (ref "R25") (pin "1") (pinfunction "1_1") (pintype "passive"))
      (node (ref "R3") (pin "1") (pinfunction "1_1") (pintype "passive"))
      (node (ref "R4") (pin "1") (pinfunction "1_1") (pintype "passive"))
      (node (ref "R5") (pin "1") (pinfunction "1_1") (pintype "passive"))
      (node (ref "R7") (pin "1") (pinfunction "1_1") (pintype "passive"))
      (node (ref "U1") (pin "14") (pinfunction "VDD_14") (pintype "power_in"))
      (node (ref "U1") (pin "3") (pinfunction "AVDD_3") (pintype "power_in"))
      (node (ref "U2") (pin "1") (pinfunction "VDDIO_1") (pintype "power_in"))
      (node (ref "U2") (pin "10") (pinfunction "VDD_10") (pintype "power_in"))
      (node (ref "U2") (pin "6") (pinfunction "CSB_6") (pintype "input"))
      (node (ref "U3") (pin "12") (pinfunction "CS_12") (pintype "input"))
      (node (ref "U3") (pin "5") (pinfunction "VDDIO_5") (pintype "power_in"))
      (node (ref "U3") (pin "8") (pinfunction "VDD_8") (pintype "power_in"))
    )
    (net (code "55") (name "unconnected-(J2-Pad6)") (class "Default")
      (node (ref "J2") (pin "6") (pinfunction "6_6") (pintype "passive+no_connect"))
    )
    (net (code "56") (name "unconnected-(S-Pad3)") (class "Default")
      (node (ref "S") (pin "3") (pinfunction "3_3") (pintype "passive"))
    )
    (net (code "57") (name "unconnected-(U1-DCC-Pad15)") (class "Default")
      (node (ref "U1") (pin "15") (pinfunction "DCC_15") (pintype "power_in"))
    )
    (net (code "58") (name "unconnected-(U1-DEC2-Pad41)") (class "Default")
      (node (ref "U1") (pin "41") (pinfunction "DEC2_41") (pintype "power_in"))
    )
    (net (code "59") (name "unconnected-(U3-SCX-Pad3)") (class "Default")
      (node (ref "U3") (pin "3") (pinfunction "SCX_3") (pintype "bidirectional+no_connect"))
    )
    (net (code "60") (name "unconnected-(U3-SDX-Pad2)") (class "Default")
      (node (ref "U3") (pin "2") (pinfunction "SDX_2") (pintype "bidirectional+no_connect"))
    )
  )
)
